# rapidshark-motor-connector-mk-1_2.net
KiCad netlist of a schematic drawn in EAGLE
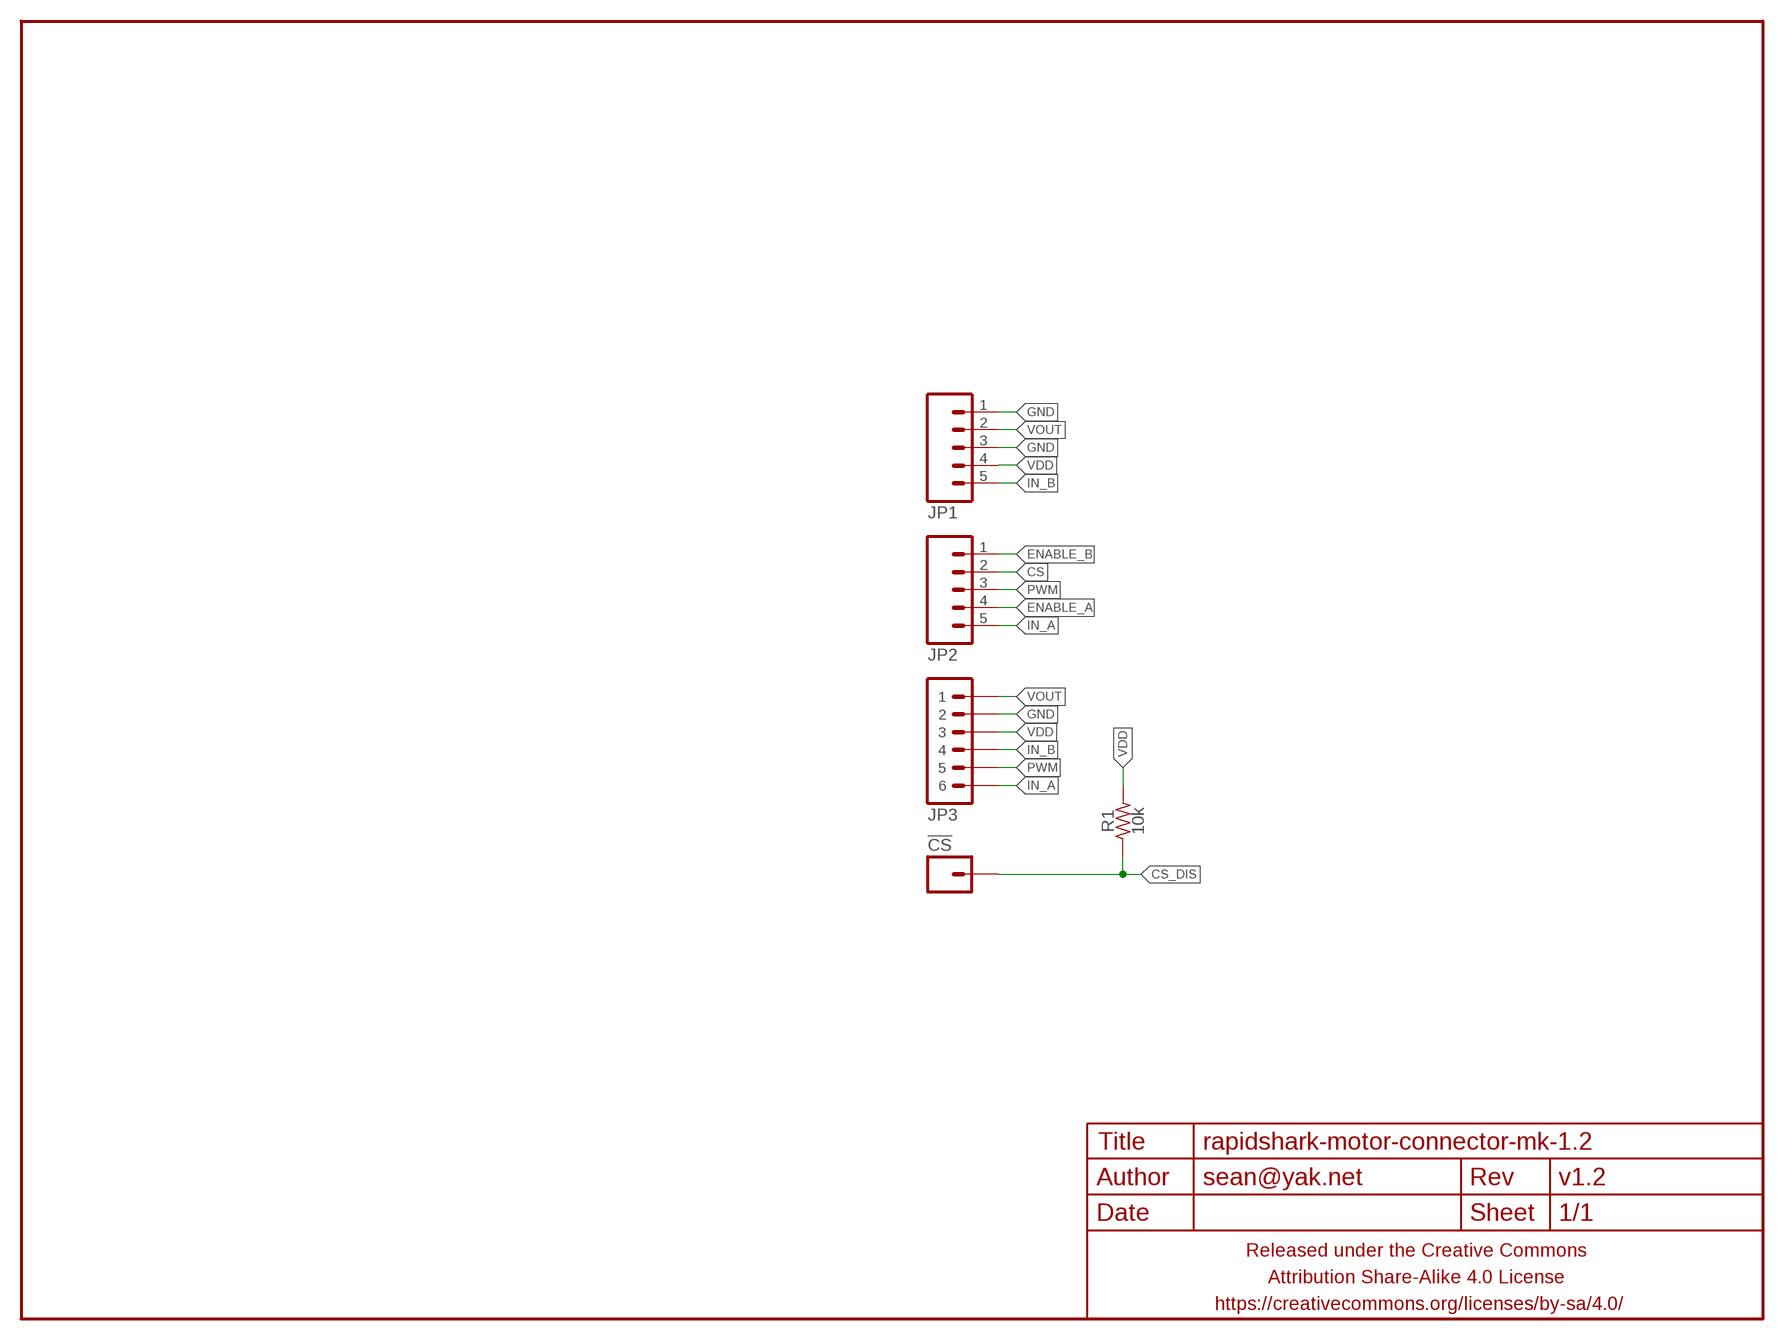
[diagram p0: schematic, sheet 1]

(export (version "E")
  (design (tool "Eeschema 10.0.6"))
  (components
    (comp (ref "!CS")
      (value "M01PTH-1MM")
      (footprint "eagle-import:1X01-1MM-NS")
      (libsource (lib "eagle-import") (part "M01PTH-1MM"))
    )
    (comp (ref "FRAME1")
      (value "FRAME-LETTERNO_PACKAGE")
      (footprint "eagle-import:DUMMY")
      (fields (field (name "DESIGNER") "sean@yak.net") (field (name "VERSION") "v1.2"))
      (libsource (lib "eagle-import") (part "FRAME-LETTERNO_PACKAGE"))
    )
    (comp (ref "JP1")
      (value "M05NO_SILK")
      (footprint "eagle-import:1X05_NO_SILK")
      (libsource (lib "eagle-import") (part "M05NO_SILK"))
    )
    (comp (ref "JP2")
      (value "M05NO_SILK")
      (footprint "eagle-import:1X05_NO_SILK")
      (libsource (lib "eagle-import") (part "M05NO_SILK"))
    )
    (comp (ref "JP3")
      (value "M06JST-PH-PTH-RA")
      (footprint "eagle-import:JST-6-PH-RA-PTH")
      (libsource (lib "eagle-import") (part "M06JST-PH-PTH-RA"))
    )
    (comp (ref "R1")
      (value "10k")
      (footprint "eagle-import:RESISTOR-AXIAL-PTH-5.08MM")
      (libsource (lib "eagle-import") (part "RESISTORPTH-AXIAL-5.08MM"))
    )
  )
  (nets
    (net (code "1") (name "CS") (class "Default")
      (node (ref "JP2") (pin "2") (pinfunction "2_2") (pintype "passive"))
    )
    (net (code "2") (name "CS_DIS") (class "Default")
      (node (ref "!CS") (pin "1") (pinfunction "1_1") (pintype "passive"))
      (node (ref "R1") (pin "P$1") (pinfunction "1_P$1") (pintype "passive"))
    )
    (net (code "3") (name "ENABLE_A") (class "Default")
      (node (ref "JP2") (pin "4") (pinfunction "4_4") (pintype "passive"))
    )
    (net (code "4") (name "ENABLE_B") (class "Default")
      (node (ref "JP2") (pin "1") (pinfunction "1_1") (pintype "passive"))
    )
    (net (code "5") (name "GND") (class "Default")
      (node (ref "JP1") (pin "1") (pinfunction "1_1") (pintype "passive"))
      (node (ref "JP1") (pin "3") (pinfunction "3_3") (pintype "passive"))
      (node (ref "JP3") (pin "2") (pinfunction "2_2") (pintype "passive"))
    )
    (net (code "6") (name "IN_A") (class "Default")
      (node (ref "JP2") (pin "5") (pinfunction "5_5") (pintype "passive"))
      (node (ref "JP3") (pin "6") (pinfunction "6_6") (pintype "passive"))
    )
    (net (code "7") (name "IN_B") (class "Default")
      (node (ref "JP1") (pin "5") (pinfunction "5_5") (pintype "passive"))
      (node (ref "JP3") (pin "4") (pinfunction "4_4") (pintype "passive"))
    )
    (net (code "8") (name "PWM") (class "Default")
      (node (ref "JP2") (pin "3") (pinfunction "3_3") (pintype "passive"))
      (node (ref "JP3") (pin "5") (pinfunction "5_5") (pintype "passive"))
    )
    (net (code "9") (name "VDD") (class "Default")
      (node (ref "JP1") (pin "4") (pinfunction "4_4") (pintype "passive"))
      (node (ref "JP3") (pin "3") (pinfunction "3_3") (pintype "passive"))
      (node (ref "R1") (pin "P$2") (pinfunction "2_P$2") (pintype "passive"))
    )
    (net (code "10") (name "VOUT") (class "Default")
      (node (ref "JP1") (pin "2") (pinfunction "2_2") (pintype "passive"))
      (node (ref "JP3") (pin "1") (pinfunction "1_1") (pintype "passive"))
    )
  )
)
